# 10_-_CPU_-_JTAG_CONTROL.net
KiCad netlist of a schematic drawn in Altium Designer
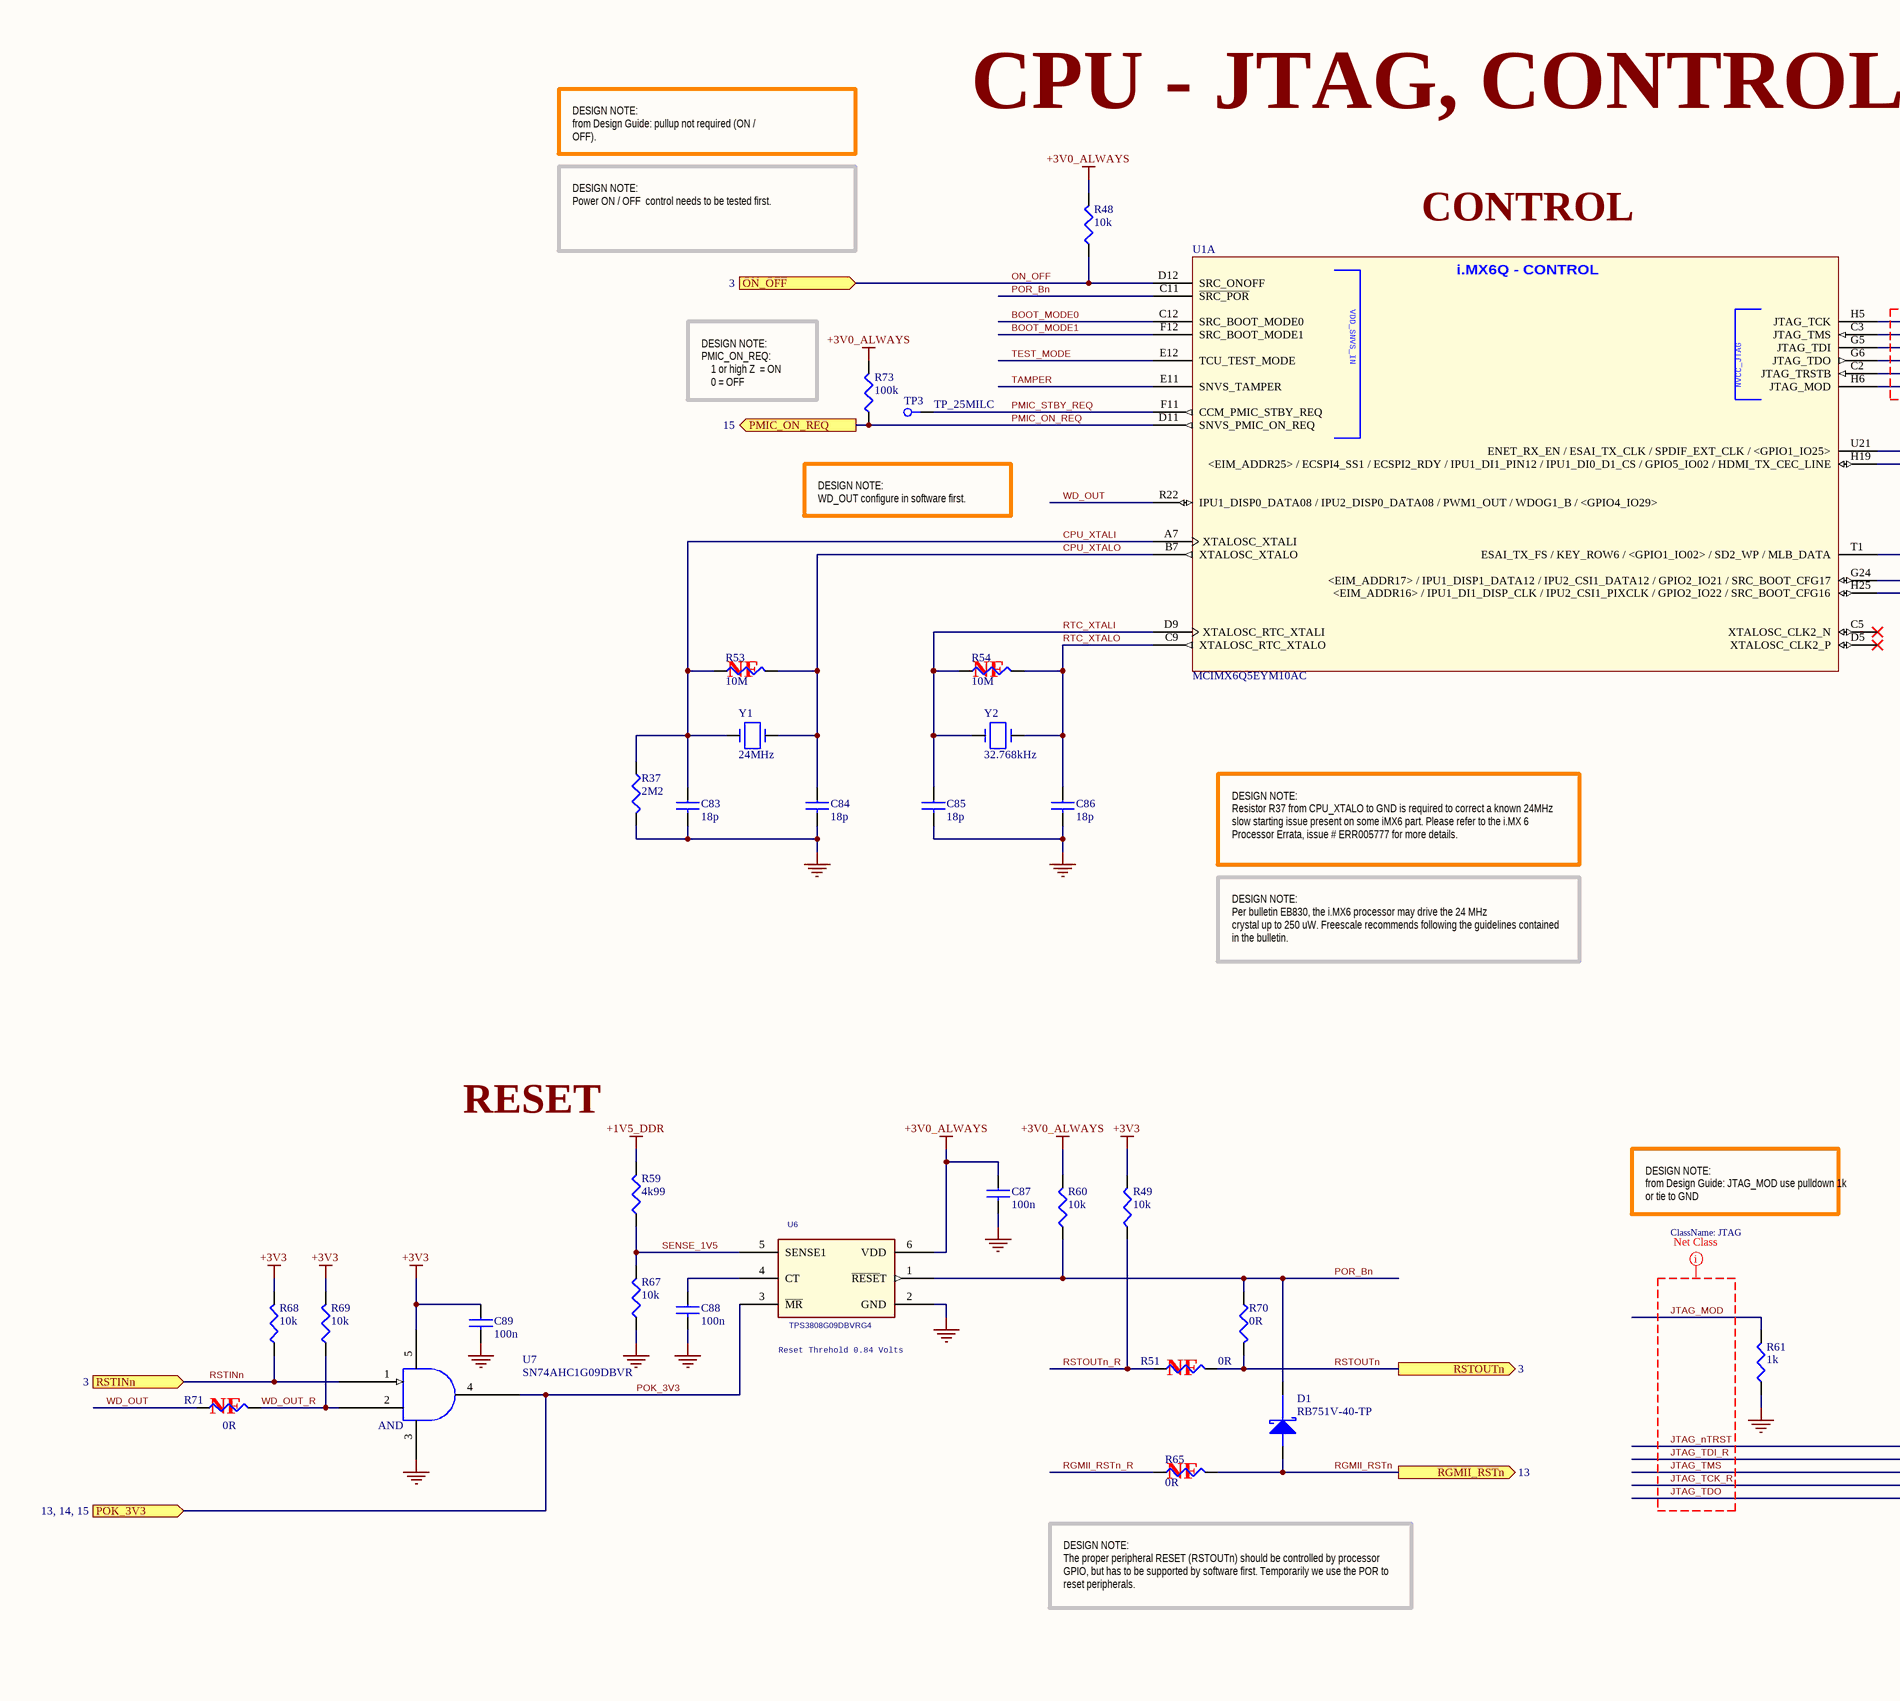
[diagram p0: [10] - CPU - JTAG, CONTROL.SchDoc, left]
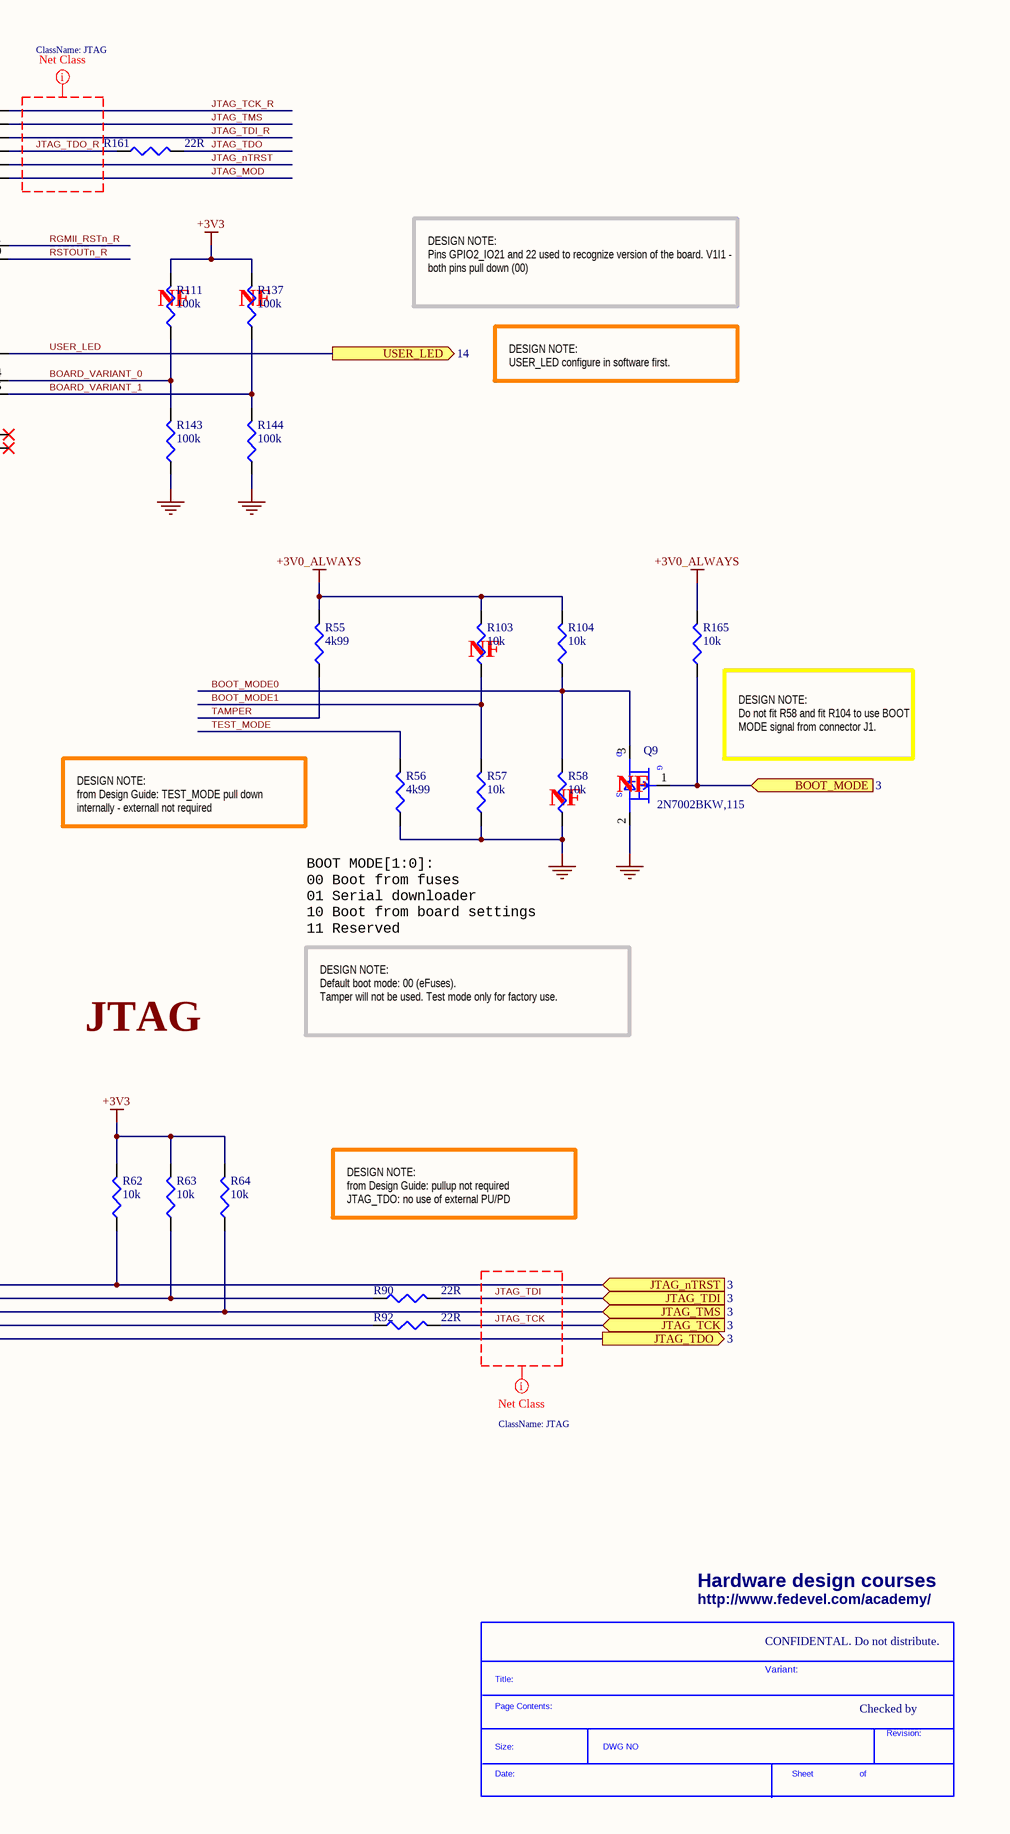
[diagram p1: [10] - CPU - JTAG, CONTROL.SchDoc, right]

(export (version "E")
  (design (tool "Eeschema 10.0.6"))
  (components
    (comp (ref "C83")
      (value "18p")
      (footprint "C0402")
      (description "CAP CER 18PF 50V C0G 5% 0402")
      (fields
        (field (name "MANUFACTURER") "TDK Corporation")
        (field (name "MANUFACTURER PART NUMBER") "C1005C0G1H180J")
      )
      (libsource (lib "Integrated_Library_RF_FEB_2012") (part "C1005C0G1H180J"))
    )
    (comp (ref "C84")
      (value "18p")
      (footprint "C0402")
      (description "CAP CER 18PF 50V C0G 5% 0402")
      (fields
        (field (name "MANUFACTURER") "TDK Corporation")
        (field (name "MANUFACTURER PART NUMBER") "C1005C0G1H180J")
      )
      (libsource (lib "Integrated_Library_RF_FEB_2012") (part "C1005C0G1H180J"))
    )
    (comp (ref "C85")
      (value "18p")
      (footprint "C0402")
      (description "CAP CER 18PF 50V C0G 5% 0402")
      (fields
        (field (name "MANUFACTURER") "TDK Corporation")
        (field (name "MANUFACTURER PART NUMBER") "C1005C0G1H180J")
      )
      (libsource (lib "Integrated_Library_RF_FEB_2012") (part "C1005C0G1H180J"))
    )
    (comp (ref "C86")
      (value "18p")
      (footprint "C0402")
      (description "CAP CER 18PF 50V C0G 5% 0402")
      (fields
        (field (name "MANUFACTURER") "TDK Corporation")
        (field (name "MANUFACTURER PART NUMBER") "C1005C0G1H180J")
      )
      (libsource (lib "Integrated_Library_RF_FEB_2012") (part "C1005C0G1H180J"))
    )
    (comp (ref "C87")
      (value "100n")
      (footprint "C0402")
      (description "CAP CER .10UF 50V X5R 10% 0402")
      (fields
        (field (name "MANUFACTURER") "TDK Corporation")
        (field (name "MANUFACTURER PART NUMBER") "C1005X5R1H104K")
      )
      (libsource (lib "Integrated_Library_RF_FEB_2012") (part "C1005X5R1H104K"))
    )
    (comp (ref "C88")
      (value "100n")
      (footprint "C0402")
      (description "CAP CER .10UF 50V X5R 10% 0402")
      (fields
        (field (name "MANUFACTURER") "TDK Corporation")
        (field (name "MANUFACTURER PART NUMBER") "C1005X5R1H104K")
      )
      (libsource (lib "Integrated_Library_RF_FEB_2012") (part "C1005X5R1H104K"))
    )
    (comp (ref "C89")
      (value "100n")
      (footprint "C0402")
      (description "CAP CER .10UF 50V X5R 10% 0402")
      (fields
        (field (name "MANUFACTURER") "TDK Corporation")
        (field (name "MANUFACTURER PART NUMBER") "C1005X5R1H104K")
      )
      (libsource (lib "Integrated_Library_RF_FEB_2012") (part "C1005X5R1H104K"))
    )
    (comp (ref "D1")
      (value "RB751V-40-TP")
      (footprint "SOD323")
      (description "DIODE SCHTKY 30MA 30V SOD-323")
      (fields
        (field (name "MANUFACTURER") "Micro Commercial Co")
        (field (name ".CHECKED PCB") "RF")
        (field (name ".CHECKED SCH") "RF")
      )
      (libsource (lib "Integrated_Library_RF_FEB_2012") (part "RB751V-40-TP"))
    )
    (comp (ref "Q9")
      (value "2N7002BKW,115")
      (footprint "SC70_SOT323")
      (description "MOSFET N-CH 60V 310MA SOT323")
      (fields
        (field (name "MANUFACTURER") "NXP Semiconductors")
        (field (name ".CHECKED PCB") "RF")
        (field (name ".CHECKED SCH") "RF")
      )
      (libsource (lib "Integrated_Library_RF_FEB_2012") (part "2N7002BKW,115"))
    )
    (comp (ref "R37")
      (value "2M2")
      (footprint "R0402")
      (description "RES 2.20M OHM 1/16W 1% 0402 SMD")
      (fields
        (field (name "MANUFACTURER") "Vishay Dale")
        (field (name "MANUFACTURER PART NUMBER") "CRCW04022M20FKED")
        (field (name ".CREATOR") "MM")
      )
      (libsource (lib "Integrated_Library_RF_FEB_2012") (part "CRCW04022M20FKED"))
    )
    (comp (ref "R48")
      (value "10k")
      (footprint "R0402")
      (description "RES 10.0K OHM 1/16W 1% 0402 SMD")
      (fields
        (field (name "MANUFACTURER") "Yageo")
        (field (name "MANUFACTURER PART NUMBER") "RC0402FR-0710KL")
      )
      (libsource (lib "Integrated_Library_RF_FEB_2012") (part "RC0402FR-0710KL"))
    )
    (comp (ref "R49")
      (value "10k")
      (footprint "R0402")
      (description "RES 10.0K OHM 1/16W 1% 0402 SMD")
      (fields
        (field (name "MANUFACTURER") "Yageo")
        (field (name "MANUFACTURER PART NUMBER") "RC0402FR-0710KL")
      )
      (libsource (lib "Integrated_Library_RF_FEB_2012") (part "RC0402FR-0710KL"))
    )
    (comp (ref "R51")
      (value "0R")
      (footprint "R0402")
      (description "RES 0.0 OHM 1/16W 0402 SMD")
      (fields
        (field (name "MANUFACTURER") "Yageo")
        (field (name "MANUFACTURER PART NUMBER") "RC0402JR-070RL")
      )
      (libsource (lib "Integrated_Library_RF_FEB_2012") (part "RC0402JR-070RL"))
    )
    (comp (ref "R53")
      (value "10M")
      (footprint "R0402")
      (description "RES 10.0M OHM 1/16W 1% 0402 SMD")
      (fields
        (field (name "MANUFACTURER") "Vishay Dale")
        (field (name "MANUFACTURER PART NUMBER") "CRCW040210M0FKED")
        (field (name ".CHECKED PCB") "RF")
        (field (name ".CHECKED SCH") "RF")
      )
      (libsource (lib "Integrated_Library_RF_FEB_2012") (part "CRCW040210M0FKED"))
    )
    (comp (ref "R54")
      (value "10M")
      (footprint "R0402")
      (description "RES 10.0M OHM 1/16W 1% 0402 SMD")
      (fields
        (field (name "MANUFACTURER") "Vishay Dale")
        (field (name "MANUFACTURER PART NUMBER") "CRCW040210M0FKED")
        (field (name ".CHECKED PCB") "RF")
        (field (name ".CHECKED SCH") "RF")
      )
      (libsource (lib "Integrated_Library_RF_FEB_2012") (part "CRCW040210M0FKED"))
    )
    (comp (ref "R55")
      (value "4k99")
      (footprint "R0402")
      (description "RES TF 4.99K OHM 1% 1/16W 0402")
      (fields
        (field (name "MANUFACTURER") "Stackpole Electronics Inc")
        (field (name "MANUFACTURER PART NUMBER") "RMCF0402FT4K99")
      )
      (libsource (lib "Integrated_Library_RF_FEB_2012") (part "RMCF0402FT4K99"))
    )
    (comp (ref "R56")
      (value "4k99")
      (footprint "R0402")
      (description "RES TF 4.99K OHM 1% 1/16W 0402")
      (fields
        (field (name "MANUFACTURER") "Stackpole Electronics Inc")
        (field (name "MANUFACTURER PART NUMBER") "RMCF0402FT4K99")
      )
      (libsource (lib "Integrated_Library_RF_FEB_2012") (part "RMCF0402FT4K99"))
    )
    (comp (ref "R57")
      (value "10k")
      (footprint "R0402")
      (description "RES 10.0K OHM 1/16W 1% 0402 SMD")
      (fields
        (field (name "MANUFACTURER") "Yageo")
        (field (name "MANUFACTURER PART NUMBER") "RC0402FR-0710KL")
      )
      (libsource (lib "Integrated_Library_RF_FEB_2012") (part "RC0402FR-0710KL"))
    )
    (comp (ref "R58")
      (value "10k")
      (footprint "R0402")
      (description "RES 10.0K OHM 1/16W 1% 0402 SMD")
      (fields
        (field (name "MANUFACTURER") "Yageo")
        (field (name "MANUFACTURER PART NUMBER") "RC0402FR-0710KL")
      )
      (libsource (lib "Integrated_Library_RF_FEB_2012") (part "RC0402FR-0710KL"))
    )
    (comp (ref "R59")
      (value "4k99")
      (footprint "R0402")
      (description "RES TF 4.99K OHM 1% 1/16W 0402")
      (fields
        (field (name "MANUFACTURER") "Stackpole Electronics Inc")
        (field (name "MANUFACTURER PART NUMBER") "RMCF0402FT4K99")
      )
      (libsource (lib "Integrated_Library_RF_FEB_2012") (part "RMCF0402FT4K99"))
    )
    (comp (ref "R60")
      (value "10k")
      (footprint "R0402")
      (description "RES 10.0K OHM 1/16W 1% 0402 SMD")
      (fields
        (field (name "MANUFACTURER") "Yageo")
        (field (name "MANUFACTURER PART NUMBER") "RC0402FR-0710KL")
      )
      (libsource (lib "Integrated_Library_RF_FEB_2012") (part "RC0402FR-0710KL"))
    )
    (comp (ref "R61")
      (value "1k")
      (footprint "R0402")
      (description "RES 1.00K OHM 1/16W 1% 0402 SMD")
      (fields
        (field (name "MANUFACTURER") "Yageo")
        (field (name "MANUFACTURER PART NUMBER") "RC0402FR-071KL")
      )
      (libsource (lib "Integrated_Library_RF_FEB_2012") (part "RC0402FR-071KL"))
    )
    (comp (ref "R62")
      (value "10k")
      (footprint "R0402")
      (description "RES 10.0K OHM 1/16W 1% 0402 SMD")
      (fields
        (field (name "MANUFACTURER") "Yageo")
        (field (name "MANUFACTURER PART NUMBER") "RC0402FR-0710KL")
      )
      (libsource (lib "Integrated_Library_RF_FEB_2012") (part "RC0402FR-0710KL"))
    )
    (comp (ref "R63")
      (value "10k")
      (footprint "R0402")
      (description "RES 10.0K OHM 1/16W 1% 0402 SMD")
      (fields
        (field (name "MANUFACTURER") "Yageo")
        (field (name "MANUFACTURER PART NUMBER") "RC0402FR-0710KL")
      )
      (libsource (lib "Integrated_Library_RF_FEB_2012") (part "RC0402FR-0710KL"))
    )
    (comp (ref "R64")
      (value "10k")
      (footprint "R0402")
      (description "RES 10.0K OHM 1/16W 1% 0402 SMD")
      (fields
        (field (name "MANUFACTURER") "Yageo")
        (field (name "MANUFACTURER PART NUMBER") "RC0402FR-0710KL")
      )
      (libsource (lib "Integrated_Library_RF_FEB_2012") (part "RC0402FR-0710KL"))
    )
    (comp (ref "R65")
      (value "0R")
      (footprint "R0402")
      (description "RES 0.0 OHM 1/16W 0402 SMD")
      (fields
        (field (name "MANUFACTURER") "Yageo")
        (field (name "MANUFACTURER PART NUMBER") "RC0402JR-070RL")
      )
      (libsource (lib "Integrated_Library_RF_FEB_2012") (part "RC0402JR-070RL"))
    )
    (comp (ref "R67")
      (value "10k")
      (footprint "R0402")
      (description "RES 10.0K OHM 1/16W 1% 0402 SMD")
      (fields
        (field (name "MANUFACTURER") "Yageo")
        (field (name "MANUFACTURER PART NUMBER") "RC0402FR-0710KL")
      )
      (libsource (lib "Integrated_Library_RF_FEB_2012") (part "RC0402FR-0710KL"))
    )
    (comp (ref "R68")
      (value "10k")
      (footprint "R0402")
      (description "RES 10.0K OHM 1/16W 1% 0402 SMD")
      (fields
        (field (name "MANUFACTURER") "Yageo")
        (field (name "MANUFACTURER PART NUMBER") "RC0402FR-0710KL")
      )
      (libsource (lib "Integrated_Library_RF_FEB_2012") (part "RC0402FR-0710KL"))
    )
    (comp (ref "R69")
      (value "10k")
      (footprint "R0402")
      (description "RES 10.0K OHM 1/16W 1% 0402 SMD")
      (fields
        (field (name "MANUFACTURER") "Yageo")
        (field (name "MANUFACTURER PART NUMBER") "RC0402FR-0710KL")
      )
      (libsource (lib "Integrated_Library_RF_FEB_2012") (part "RC0402FR-0710KL"))
    )
    (comp (ref "R70")
      (value "0R")
      (footprint "R0402")
      (description "RES 0.0 OHM 1/16W 0402 SMD")
      (fields
        (field (name "MANUFACTURER") "Yageo")
        (field (name "MANUFACTURER PART NUMBER") "RC0402JR-070RL")
      )
      (libsource (lib "Integrated_Library_RF_FEB_2012") (part "RC0402JR-070RL"))
    )
    (comp (ref "R71")
      (value "0R")
      (footprint "R0402")
      (description "RES 0.0 OHM 1/16W 0402 SMD")
      (fields
        (field (name "MANUFACTURER") "Yageo")
        (field (name "MANUFACTURER PART NUMBER") "RC0402JR-070RL")
      )
      (libsource (lib "Integrated_Library_RF_FEB_2012") (part "RC0402JR-070RL"))
    )
    (comp (ref "R73")
      (value "100k")
      (footprint "R0402")
      (description "RES 100K OHM 1/16W 1% 0402 SMD")
      (fields
        (field (name "MANUFACTURER") "Stackpole Electronics Inc")
        (field (name "MANUFACTURER PART NUMBER") "RMCF0402FT100K")
      )
      (libsource (lib "Integrated_Library_RF_FEB_2012") (part "RMCF0402FT100K"))
    )
    (comp (ref "R90")
      (value "22R")
      (footprint "R0402")
      (description "RES 22.0 OHM 1/16W 1% 0402 SMD")
      (fields
        (field (name "MANUFACTURER") "Yageo")
        (field (name "MANUFACTURER PART NUMBER") "RC0402FR-0722RL")
      )
      (libsource (lib "Integrated_Library_RF_FEB_2012") (part "RC0402FR-0722RL"))
    )
    (comp (ref "R92")
      (value "22R")
      (footprint "R0402")
      (description "RES 22.0 OHM 1/16W 1% 0402 SMD")
      (fields
        (field (name "MANUFACTURER") "Yageo")
        (field (name "MANUFACTURER PART NUMBER") "RC0402FR-0722RL")
      )
      (libsource (lib "Integrated_Library_RF_FEB_2012") (part "RC0402FR-0722RL"))
    )
    (comp (ref "R103")
      (value "10k")
      (footprint "R0402")
      (description "RES 10.0K OHM 1/16W 1% 0402 SMD")
      (fields
        (field (name "MANUFACTURER") "Yageo")
        (field (name "MANUFACTURER PART NUMBER") "RC0402FR-0710KL")
      )
      (libsource (lib "Integrated_Library_RF_FEB_2012") (part "RC0402FR-0710KL"))
    )
    (comp (ref "R104")
      (value "10k")
      (footprint "R0402")
      (description "RES 10.0K OHM 1/16W 1% 0402 SMD")
      (fields
        (field (name "MANUFACTURER") "Yageo")
        (field (name "MANUFACTURER PART NUMBER") "RC0402FR-0710KL")
      )
      (libsource (lib "Integrated_Library_RF_FEB_2012") (part "RC0402FR-0710KL"))
    )
    (comp (ref "R111")
      (value "100k")
      (footprint "R0402")
      (description "RES 100K OHM 1/16W 1% 0402 SMD")
      (fields
        (field (name "MANUFACTURER") "Stackpole Electronics Inc")
        (field (name "MANUFACTURER PART NUMBER") "RMCF0402FT100K")
      )
      (libsource (lib "Integrated_Library_RF_FEB_2012") (part "RMCF0402FT100K"))
    )
    (comp (ref "R137")
      (value "100k")
      (footprint "R0402")
      (description "RES 100K OHM 1/16W 1% 0402 SMD")
      (fields
        (field (name "MANUFACTURER") "Stackpole Electronics Inc")
        (field (name "MANUFACTURER PART NUMBER") "RMCF0402FT100K")
      )
      (libsource (lib "Integrated_Library_RF_FEB_2012") (part "RMCF0402FT100K"))
    )
    (comp (ref "R143")
      (value "100k")
      (footprint "R0402")
      (description "RES 100K OHM 1/16W 1% 0402 SMD")
      (fields
        (field (name "MANUFACTURER") "Stackpole Electronics Inc")
        (field (name "MANUFACTURER PART NUMBER") "RMCF0402FT100K")
      )
      (libsource (lib "Integrated_Library_RF_FEB_2012") (part "RMCF0402FT100K"))
    )
    (comp (ref "R144")
      (value "100k")
      (footprint "R0402")
      (description "RES 100K OHM 1/16W 1% 0402 SMD")
      (fields
        (field (name "MANUFACTURER") "Stackpole Electronics Inc")
        (field (name "MANUFACTURER PART NUMBER") "RMCF0402FT100K")
      )
      (libsource (lib "Integrated_Library_RF_FEB_2012") (part "RMCF0402FT100K"))
    )
    (comp (ref "R161")
      (value "22R")
      (footprint "R0402")
      (description "RES 22.0 OHM 1/16W 1% 0402 SMD")
      (fields
        (field (name "MANUFACTURER") "Yageo")
        (field (name "MANUFACTURER PART NUMBER") "RC0402FR-0722RL")
      )
      (libsource (lib "Integrated_Library_RF_FEB_2012") (part "RC0402FR-0722RL"))
    )
    (comp (ref "R165")
      (value "10k")
      (footprint "R0402")
      (description "RES 10.0K OHM 1/16W 1% 0402 SMD")
      (fields
        (field (name "MANUFACTURER") "Yageo")
        (field (name "MANUFACTURER PART NUMBER") "RC0402FR-0710KL")
      )
      (libsource (lib "Integrated_Library_RF_FEB_2012") (part "RC0402FR-0710KL"))
    )
    (comp (ref "TP3")
      (value "TP_25MILC")
      (footprint "TP_25C")
      (description "Test Point 25mil")
      (libsource (lib "Integrated_Library_RF_FEB_2012") (part "TP_25MILC"))
    )
    (comp (ref "U1")
      (value "MCIMX6Q5EYM10AC")
      (footprint "PBGA624")
      (description "IC MCU 32BIT ARM QUAD 624FCBGA")
      (fields
        (field (name "MANUFACTURER") "Freescale Semiconductor")
        (field (name ".CREATOR") "MM")
        (field (name ".CHECKED PCB") "MM, checked by RF")
        (field (name ".CHECKED SCH") "MM")
      )
      (libsource (lib "Schlib_RF") (part "MCIMX6Q5EYM10AC"))
    )
    (comp (ref "U6")
      (value "TPS3808G09DBVRG4")
      (footprint "DBV_SOT_23_6")
      (description "IC VOLT SUPERVISOR 0.9V SOT23-6")
      (fields (field (name "PART #") "102020-0009R") (field (name "MANUFACTURER") "Texas Instruments"))
      (libsource (lib "Integrated_Library_RF_FEB_2012") (part "TPS3808G09DBVR"))
    )
    (comp (ref "U7")
      (value "SN74AHC1G09DBVR")
      (footprint "DBV_SOT_23_5")
      (description "IC GATE AND SGL 2INP SOT23-5")
      (fields
        (field (name "MANUFACTURER") "Texas Instruments")
        (field (name ".CREATOR") "MM")
        (field (name ".CHECKED PCB") "RF, used by MM")
        (field (name ".CHECKED SCH") "MM, checked by RF")
      )
      (libsource (lib "Schlib_RF") (part "SN74AHC1G09DBVR"))
    )
    (comp (ref "Y1")
      (value "24MHz")
      (footprint "ABM7_v1_1")
      (description "CRYSTAL 24.0000MHZ 18PF SMD")
      (fields
        (field (name "MANUFACTURER") "Abracon Corporation")
        (field (name "MANUFACTURER PART NUMBER") "ABM7-24.000MHZ-D-2-Y-T")
        (field (name ".CREATOR") "MM")
        (field (name ".CHECKED PCB") "RF, used by MM")
        (field (name ".CHECKED SCH") "MM, checked by RF")
      )
      (libsource (lib "Schlib_RF") (part "ABM7-24.000MHZ-D-2-Y-T"))
    )
    (comp (ref "Y2")
      (value "32.768kHz")
      (footprint "ABS06")
      (description "CRYSTAL 32.768 KHZ 9.0 PF SMD")
      (fields
        (field (name "MANUFACTURER") "Abracon Corporation")
        (field (name "MANUFACTURER PART NUMBER") "ABS06-32.768KHZ-9-1-T")
      )
      (libsource (lib "Integrated_Library_RF_FEB_2012") (part "ABS06-32.768KHZ-9-1-T"))
    )
  )
  (nets
    (net (code "1") (name "+1V5_DDR") (class "Default")
      (node (ref "R59") (pin "2") (pinfunction "2_2") (pintype "passive"))
    )
    (net (code "2") (name "+3V0_ALWAYS") (class "Default")
      (node (ref "C87") (pin "1") (pinfunction "1_1") (pintype "passive"))
      (node (ref "R103") (pin "2") (pinfunction "2_2") (pintype "passive"))
      (node (ref "R104") (pin "2") (pinfunction "2_2") (pintype "passive"))
      (node (ref "R165") (pin "2") (pinfunction "2_2") (pintype "passive"))
      (node (ref "R48") (pin "2") (pinfunction "2_2") (pintype "passive"))
      (node (ref "R55") (pin "2") (pinfunction "2_2") (pintype "passive"))
      (node (ref "R60") (pin "2") (pinfunction "2_2") (pintype "passive"))
      (node (ref "R73") (pin "2") (pinfunction "2_2") (pintype "passive"))
      (node (ref "U6") (pin "6") (pinfunction "VDD_6") (pintype "passive"))
    )
    (net (code "3") (name "+3V3") (class "Default")
      (node (ref "C89") (pin "1") (pinfunction "1_1") (pintype "passive"))
      (node (ref "R111") (pin "2") (pinfunction "2_2") (pintype "passive"))
      (node (ref "R137") (pin "2") (pinfunction "2_2") (pintype "passive"))
      (node (ref "R49") (pin "2") (pinfunction "2_2") (pintype "passive"))
      (node (ref "R62") (pin "2") (pinfunction "2_2") (pintype "passive"))
      (node (ref "R63") (pin "2") (pinfunction "2_2") (pintype "passive"))
      (node (ref "R64") (pin "2") (pinfunction "2_2") (pintype "passive"))
      (node (ref "R68") (pin "2") (pinfunction "2_2") (pintype "passive"))
      (node (ref "R69") (pin "2") (pinfunction "2_2") (pintype "passive"))
      (node (ref "U7") (pin "5") (pinfunction "VCC_5") (pintype "power_in"))
    )
    (net (code "4") (name "/BOARD_VARIANT_0") (class "Default")
      (node (ref "R111") (pin "1") (pinfunction "1_1") (pintype "passive"))
      (node (ref "R143") (pin "2") (pinfunction "2_2") (pintype "passive"))
      (node (ref "U1") (pin "G24") (pinfunction "<EIM_ADDR17>_/_IPU1_DISP1_DATA12_/_IPU2_CSI1_DATA12_/_GPIO2_IO21_/_SRC_BOOT_CFG17_G24") (pintype "bidirectional"))
    )
    (net (code "5") (name "/BOARD_VARIANT_1") (class "Default")
      (node (ref "R137") (pin "1") (pinfunction "1_1") (pintype "passive"))
      (node (ref "R144") (pin "2") (pinfunction "2_2") (pintype "passive"))
      (node (ref "U1") (pin "H25") (pinfunction "<EIM_ADDR16>_/_IPU1_DI1_DISP_CLK_/_IPU2_CSI1_PIXCLK_/_GPIO2_IO22_/_SRC_BOOT_CFG16_H25") (pintype "bidirectional"))
    )
    (net (code "6") (name "/BOOT_MODE") (class "Default")
      (node (ref "Q9") (pin "1") (pinfunction "GATE_1") (pintype "passive"))
      (node (ref "R165") (pin "1") (pinfunction "1_1") (pintype "passive"))
    )
    (net (code "7") (name "/BOOT_MODE0") (class "Default")
      (node (ref "Q9") (pin "3") (pinfunction "DRAIN_3") (pintype "passive"))
      (node (ref "R104") (pin "1") (pinfunction "1_1") (pintype "passive"))
      (node (ref "R58") (pin "2") (pinfunction "2_2") (pintype "passive"))
      (node (ref "U1") (pin "C12") (pinfunction "SRC_BOOT_MODE0_C12") (pintype "passive"))
    )
    (net (code "8") (name "/BOOT_MODE1") (class "Default")
      (node (ref "R103") (pin "1") (pinfunction "1_1") (pintype "passive"))
      (node (ref "R57") (pin "2") (pinfunction "2_2") (pintype "passive"))
      (node (ref "U1") (pin "F12") (pinfunction "SRC_BOOT_MODE1_F12") (pintype "passive"))
    )
    (net (code "9") (name "/CPU_XTALI") (class "Default")
      (node (ref "C83") (pin "1") (pinfunction "1_1") (pintype "passive"))
      (node (ref "R37") (pin "1") (pinfunction "1_1") (pintype "passive"))
      (node (ref "R53") (pin "1") (pinfunction "1_1") (pintype "passive"))
      (node (ref "U1") (pin "A7") (pinfunction "XTALOSC_XTALI_A7") (pintype "passive"))
      (node (ref "Y1") (pin "1") (pinfunction "1_1") (pintype "passive"))
    )
    (net (code "10") (name "/CPU_XTALO") (class "Default")
      (node (ref "C84") (pin "1") (pinfunction "1_1") (pintype "passive"))
      (node (ref "R53") (pin "2") (pinfunction "2_2") (pintype "passive"))
      (node (ref "U1") (pin "B7") (pinfunction "XTALOSC_XTALO_B7") (pintype "output"))
      (node (ref "Y1") (pin "2") (pinfunction "2_2") (pintype "passive"))
    )
    (net (code "11") (name "/JTAG_MOD") (class "Default")
      (node (ref "R61") (pin "2") (pinfunction "2_2") (pintype "passive"))
      (node (ref "U1") (pin "H6") (pinfunction "JTAG_MOD_H6") (pintype "passive"))
    )
    (net (code "12") (name "/JTAG_TCK") (class "Default")
      (node (ref "R92") (pin "2") (pinfunction "2_2") (pintype "passive"))
    )
    (net (code "13") (name "/JTAG_TCK_R") (class "Default")
      (node (ref "R92") (pin "1") (pinfunction "1_1") (pintype "passive"))
      (node (ref "U1") (pin "H5") (pinfunction "JTAG_TCK_H5") (pintype "passive"))
    )
    (net (code "14") (name "/JTAG_TDI") (class "Default")
      (node (ref "R90") (pin "2") (pinfunction "2_2") (pintype "passive"))
    )
    (net (code "15") (name "/JTAG_TDI_R") (class "Default")
      (node (ref "R63") (pin "1") (pinfunction "1_1") (pintype "passive"))
      (node (ref "R90") (pin "1") (pinfunction "1_1") (pintype "passive"))
      (node (ref "U1") (pin "G5") (pinfunction "JTAG_TDI_G5") (pintype "passive"))
    )
    (net (code "16") (name "/JTAG_TDO") (class "Default")
      (node (ref "R161") (pin "2") (pinfunction "2_2") (pintype "passive"))
    )
    (net (code "17") (name "/JTAG_TDO_R") (class "Default")
      (node (ref "R161") (pin "1") (pinfunction "1_1") (pintype "passive"))
      (node (ref "U1") (pin "G6") (pinfunction "JTAG_TDO_G6") (pintype "output"))
    )
    (net (code "18") (name "/JTAG_TMS") (class "Default")
      (node (ref "R64") (pin "1") (pinfunction "1_1") (pintype "passive"))
      (node (ref "U1") (pin "C3") (pinfunction "JTAG_TMS_C3") (pintype "input"))
    )
    (net (code "19") (name "/JTAG_nTRST") (class "Default")
      (node (ref "R62") (pin "1") (pinfunction "1_1") (pintype "passive"))
      (node (ref "U1") (pin "C2") (pinfunction "JTAG_TRSTB_C2") (pintype "input"))
    )
    (net (code "20") (name "/ON_OFF") (class "Default")
      (node (ref "R48") (pin "1") (pinfunction "1_1") (pintype "passive"))
      (node (ref "U1") (pin "D12") (pinfunction "SRC_ONOFF_D12") (pintype "passive"))
    )
    (net (code "21") (name "/PMIC_ON_REQ") (class "Default")
      (node (ref "R73") (pin "1") (pinfunction "1_1") (pintype "passive"))
      (node (ref "U1") (pin "D11") (pinfunction "SNVS_PMIC_ON_REQ_D11") (pintype "output"))
    )
    (net (code "22") (name "/PMIC_STBY_REQ") (class "Default")
      (node (ref "TP3") (pin "1") (pinfunction "1_1") (pintype "passive"))
      (node (ref "U1") (pin "F11") (pinfunction "CCM_PMIC_STBY_REQ_F11") (pintype "output"))
    )
    (net (code "23") (name "/POK_3V3") (class "Default")
      (node (ref "U6") (pin "3") (pinfunction "~{MR}_3") (pintype "passive"))
      (node (ref "U7") (pin "4") (pinfunction "Y_4") (pintype "passive"))
    )
    (net (code "24") (name "/POR_Bn") (class "Default")
      (node (ref "D1") (pin "1") (pinfunction "cathode_1") (pintype "passive"))
      (node (ref "R60") (pin "1") (pinfunction "1_1") (pintype "passive"))
      (node (ref "R70") (pin "1") (pinfunction "1_1") (pintype "passive"))
      (node (ref "U1") (pin "C11") (pinfunction "~{SRC_POR}_C11") (pintype "passive"))
      (node (ref "U6") (pin "1") (pinfunction "~{RESE}T_1") (pintype "output"))
    )
    (net (code "25") (name "/RGMII_RSTn") (class "Default")
      (node (ref "D1") (pin "2") (pinfunction "ANODE_2") (pintype "passive"))
      (node (ref "R65") (pin "2") (pinfunction "2_2") (pintype "passive"))
    )
    (net (code "26") (name "/RGMII_RSTn_R") (class "Default")
      (node (ref "R65") (pin "1") (pinfunction "1_1") (pintype "passive"))
      (node (ref "U1") (pin "U21") (pinfunction "ENET_RX_EN_/_ESAI_TX_CLK_/_SPDIF_EXT_CLK_/_<GPIO1_IO25>_U21") (pintype "passive"))
    )
    (net (code "27") (name "/RSTINn") (class "Default")
      (node (ref "R68") (pin "1") (pinfunction "1_1") (pintype "passive"))
      (node (ref "U7") (pin "1") (pinfunction "A_1") (pintype "input"))
    )
    (net (code "28") (name "/RSTOUTn") (class "Default")
      (node (ref "R51") (pin "2") (pinfunction "2_2") (pintype "passive"))
      (node (ref "R70") (pin "2") (pinfunction "2_2") (pintype "passive"))
    )
    (net (code "29") (name "/RSTOUTn_R") (class "Default")
      (node (ref "R49") (pin "1") (pinfunction "1_1") (pintype "passive"))
      (node (ref "R51") (pin "1") (pinfunction "1_1") (pintype "passive"))
      (node (ref "U1") (pin "H19") (pinfunction "<EIM_ADDR25>_/_ECSPI4_SS1_/_ECSPI2_RDY_/_IPU1_DI1_PIN12_/_IPU1_DI0_D1_CS_/_GPIO5_IO02_/_HDMI_TX_CEC_LINE_H19") (pintype "bidirectional"))
    )
    (net (code "30") (name "/RTC_XTALI") (class "Default")
      (node (ref "C85") (pin "1") (pinfunction "1_1") (pintype "passive"))
      (node (ref "R54") (pin "1") (pinfunction "1_1") (pintype "passive"))
      (node (ref "U1") (pin "D9") (pinfunction "XTALOSC_RTC_XTALI_D9") (pintype "passive"))
      (node (ref "Y2") (pin "1") (pinfunction "1_1") (pintype "passive"))
    )
    (net (code "31") (name "/RTC_XTALO") (class "Default")
      (node (ref "C86") (pin "1") (pinfunction "1_1") (pintype "passive"))
      (node (ref "R54") (pin "2") (pinfunction "2_2") (pintype "passive"))
      (node (ref "U1") (pin "C9") (pinfunction "XTALOSC_RTC_XTALO_C9") (pintype "output"))
      (node (ref "Y2") (pin "2") (pinfunction "2_2") (pintype "passive"))
    )
    (net (code "32") (name "/SENSE_1V5") (class "Default")
      (node (ref "R59") (pin "1") (pinfunction "1_1") (pintype "passive"))
      (node (ref "R67") (pin "2") (pinfunction "2_2") (pintype "passive"))
      (node (ref "U6") (pin "5") (pinfunction "SENSE1_5") (pintype "passive"))
    )
    (net (code "33") (name "/TAMPER") (class "Default")
      (node (ref "R55") (pin "1") (pinfunction "1_1") (pintype "passive"))
      (node (ref "U1") (pin "E11") (pinfunction "SNVS_TAMPER_E11") (pintype "passive"))
    )
    (net (code "34") (name "/TEST_MODE") (class "Default")
      (node (ref "R56") (pin "2") (pinfunction "2_2") (pintype "passive"))
      (node (ref "U1") (pin "E12") (pinfunction "TCU_TEST_MODE_E12") (pintype "passive"))
    )
    (net (code "35") (name "/USER_LED") (class "Default")
      (node (ref "U1") (pin "T1") (pinfunction "ESAI_TX_FS_/_KEY_ROW6_/_<GPIO1_IO02>_/_SD2_WP_/_MLB_DATA_T1") (pintype "passive"))
    )
    (net (code "36") (name "/WD_OUT") (class "Default")
      (node (ref "R71") (pin "1") (pinfunction "1_1") (pintype "passive"))
      (node (ref "U1") (pin "R22") (pinfunction "IPU1_DISP0_DATA08_/_IPU2_DISP0_DATA08_/_PWM1_OUT_/_WDOG1_B_/_<GPIO4_IO29>_R22") (pintype "bidirectional"))
    )
    (net (code "37") (name "/WD_OUT_R") (class "Default")
      (node (ref "R69") (pin "1") (pinfunction "1_1") (pintype "passive"))
      (node (ref "R71") (pin "2") (pinfunction "2_2") (pintype "passive"))
      (node (ref "U7") (pin "2") (pinfunction "B_2") (pintype "passive"))
    )
    (net (code "38") (name "GND") (class "Default")
      (node (ref "C83") (pin "2") (pinfunction "2_2") (pintype "passive"))
      (node (ref "C84") (pin "2") (pinfunction "2_2") (pintype "passive"))
      (node (ref "C85") (pin "2") (pinfunction "2_2") (pintype "passive"))
      (node (ref "C86") (pin "2") (pinfunction "2_2") (pintype "passive"))
      (node (ref "C87") (pin "2") (pinfunction "2_2") (pintype "passive"))
      (node (ref "C88") (pin "2") (pinfunction "2_2") (pintype "passive"))
      (node (ref "C89") (pin "2") (pinfunction "2_2") (pintype "passive"))
      (node (ref "Q9") (pin "2") (pinfunction "SOURCE_2") (pintype "passive"))
      (node (ref "R143") (pin "1") (pinfunction "1_1") (pintype "passive"))
      (node (ref "R144") (pin "1") (pinfunction "1_1") (pintype "passive"))
      (node (ref "R37") (pin "2") (pinfunction "2_2") (pintype "passive"))
      (node (ref "R56") (pin "1") (pinfunction "1_1") (pintype "passive"))
      (node (ref "R57") (pin "1") (pinfunction "1_1") (pintype "passive"))
      (node (ref "R58") (pin "1") (pinfunction "1_1") (pintype "passive"))
      (node (ref "R61") (pin "1") (pinfunction "1_1") (pintype "passive"))
      (node (ref "R67") (pin "1") (pinfunction "1_1") (pintype "passive"))
      (node (ref "U6") (pin "2") (pinfunction "GND_2") (pintype "passive"))
      (node (ref "U7") (pin "3") (pinfunction "GND_3") (pintype "power_in"))
    )
    (net (code "39") (name "Net-(U6-CT)") (class "Default")
      (node (ref "C88") (pin "1") (pinfunction "1_1") (pintype "passive"))
      (node (ref "U6") (pin "4") (pinfunction "CT_4") (pintype "passive"))
    )
    (net (code "40") (name "unconnected-(U1A-XTALOSC_CLK2_N-PadC5)") (class "Default")
      (node (ref "U1") (pin "C5") (pinfunction "XTALOSC_CLK2_N_C5") (pintype "bidirectional+no_connect"))
    )
    (net (code "41") (name "unconnected-(U1A-XTALOSC_CLK2_P-PadD5)") (class "Default")
      (node (ref "U1") (pin "D5") (pinfunction "XTALOSC_CLK2_P_D5") (pintype "bidirectional+no_connect"))
    )
  )
)
